# TPA3255.net
KiCad netlist of a schematic drawn in EAGLE
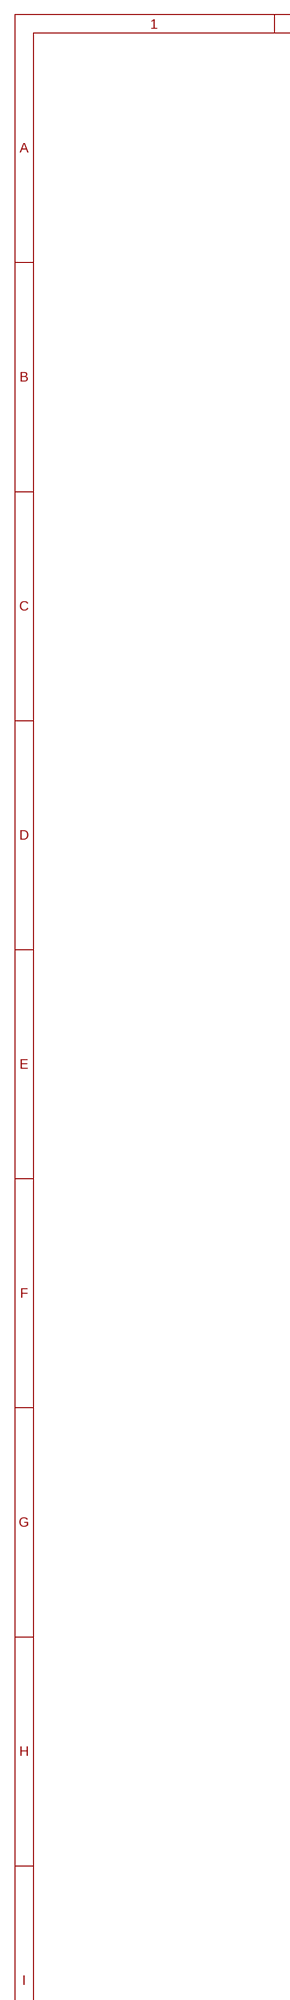
[diagram p0: schematic, sheet 1, part 1 of 2]
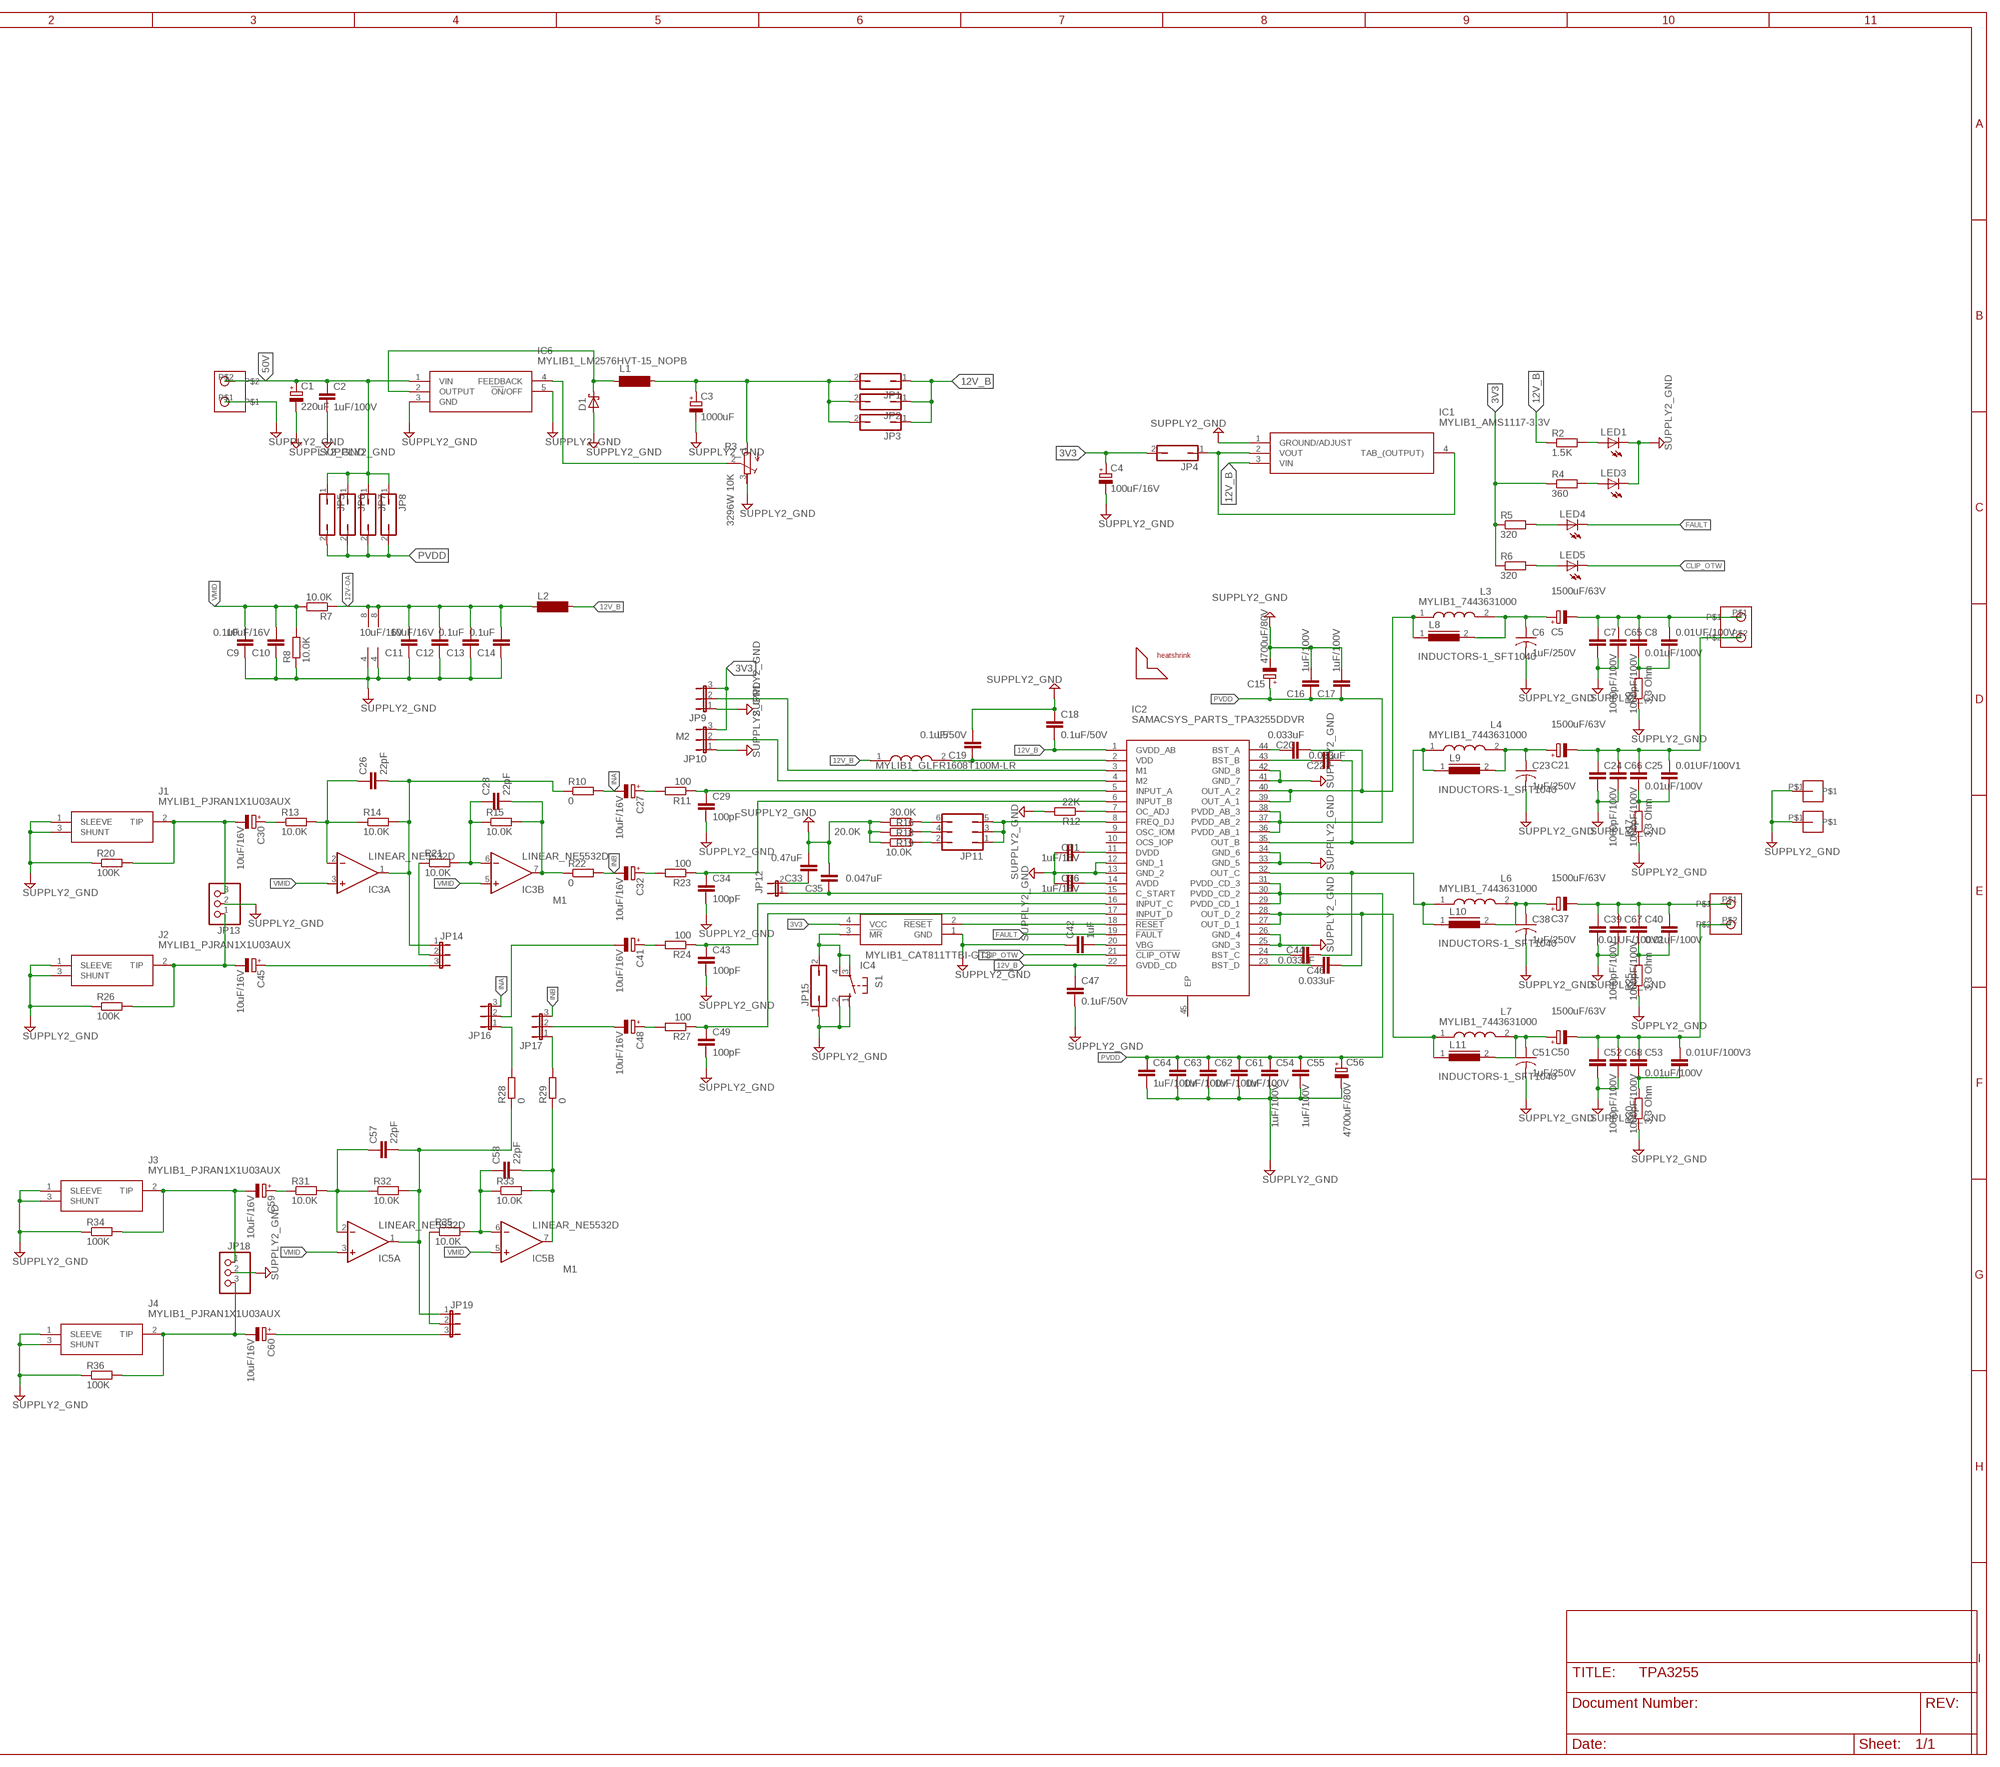
[diagram p1: schematic, sheet 1, part 2 of 2]

(export (version "E")
  (design (tool "Eeschema 10.0.6"))
  (components
    (comp (ref "0.01UF/100V")
      (value "RCL_C-EU102-054X133")
      (footprint "eagle-import:RCL_C102-054X133")
      (libsource (lib "eagle-import") (part "RCL_C-EU102-054X133"))
    )
    (comp (ref "0.01UF/100V1")
      (value "RCL_C-EU102-054X133")
      (footprint "eagle-import:RCL_C102-054X133")
      (libsource (lib "eagle-import") (part "RCL_C-EU102-054X133"))
    )
    (comp (ref "0.01UF/100V2")
      (value "RCL_C-EU102-054X133")
      (footprint "eagle-import:RCL_C102-054X133")
      (libsource (lib "eagle-import") (part "RCL_C-EU102-054X133"))
    )
    (comp (ref "0.01UF/100V3")
      (value "RCL_C-EU102-054X133")
      (footprint "eagle-import:RCL_C102-054X133")
      (libsource (lib "eagle-import") (part "RCL_C-EU102-054X133"))
    )
    (comp (ref "C1")
      (value "220uF")
      (footprint "eagle-import:RCL_E7,5-18")
      (libsource (lib "eagle-import") (part "RCL_CPOL-EUE7.5-18"))
    )
    (comp (ref "C2")
      (value "1uF/100V")
      (footprint "eagle-import:RCL_C150-054X183")
      (libsource (lib "eagle-import") (part "RCL_C-EU150-054X183"))
    )
    (comp (ref "C3")
      (value "1000uF")
      (footprint "eagle-import:RCL_E5-10,5")
      (libsource (lib "eagle-import") (part "RCL_CPOL-EUE5-10.5"))
    )
    (comp (ref "C4")
      (value "100uF/16V")
      (footprint "eagle-import:RESISTOR_PANASONIC_B_1")
      (libsource (lib "eagle-import") (part "RESISTOR_CPOL-EU?{colon}1B"))
    )
    (comp (ref "C5")
      (value "1500uF/63V")
      (footprint "eagle-import:RCL_EB22,5D")
      (libsource (lib "eagle-import") (part "RCL_CPOL-EUE10-22.5"))
    )
    (comp (ref "C6")
      (value "1uF/250V")
      (footprint "eagle-import:RCL_C225-108X268")
      (libsource (lib "eagle-import") (part "RCL_C-US225-108X268"))
    )
    (comp (ref "C7")
      (value "1000pF/100V")
      (footprint "eagle-import:RCL_C1206")
      (libsource (lib "eagle-import") (part "RCL_C-EUC1206"))
    )
    (comp (ref "C8")
      (value "0.01uF/100V")
      (footprint "eagle-import:RCL_C0603")
      (libsource (lib "eagle-import") (part "RCL_C-EUC0603"))
    )
    (comp (ref "C9")
      (value "0.1uF")
      (footprint "eagle-import:RCL_C0805")
      (libsource (lib "eagle-import") (part "RCL_C-EUC0805"))
    )
    (comp (ref "C10")
      (value "10uF/16V")
      (footprint "eagle-import:RCL_C0805")
      (libsource (lib "eagle-import") (part "RCL_C-EUC0805"))
    )
    (comp (ref "C11")
      (value "10uF/16V")
      (footprint "eagle-import:RCL_C0805")
      (libsource (lib "eagle-import") (part "RCL_C-EUC0805"))
    )
    (comp (ref "C12")
      (value "10uF/16V")
      (footprint "eagle-import:RCL_C0805")
      (libsource (lib "eagle-import") (part "RCL_C-EUC0805"))
    )
    (comp (ref "C13")
      (value "0.1uF")
      (footprint "eagle-import:RCL_C0805")
      (libsource (lib "eagle-import") (part "RCL_C-EUC0805"))
    )
    (comp (ref "C14")
      (value "0.1uF")
      (footprint "eagle-import:RCL_C0805")
      (libsource (lib "eagle-import") (part "RCL_C-EUC0805"))
    )
    (comp (ref "C15")
      (value "4700uF/80V")
      (footprint "eagle-import:RCL_EB35D")
      (libsource (lib "eagle-import") (part "RCL_CPOL-EUE10-35"))
    )
    (comp (ref "C16")
      (value "1uF/100V")
      (footprint "eagle-import:RCL_C150-054X183")
      (libsource (lib "eagle-import") (part "RCL_C-EU150-054X183"))
    )
    (comp (ref "C17")
      (value "1uF/100V")
      (footprint "eagle-import:RCL_C150-054X183")
      (libsource (lib "eagle-import") (part "RCL_C-EU150-054X183"))
    )
    (comp (ref "C18")
      (value "0.1uF/50V")
      (footprint "eagle-import:RCL_C0603")
      (libsource (lib "eagle-import") (part "RCL_C-EUC0603"))
    )
    (comp (ref "C19")
      (value "0.1uF/50V")
      (footprint "eagle-import:RCL_C0603")
      (libsource (lib "eagle-import") (part "RCL_C-EUC0603"))
    )
    (comp (ref "C20")
      (value "0.033uF")
      (footprint "eagle-import:RCL_C0603K")
      (libsource (lib "eagle-import") (part "RCL_C-EUC0603K"))
    )
    (comp (ref "C21")
      (value "1500uF/63V")
      (footprint "eagle-import:RCL_EB22,5D")
      (libsource (lib "eagle-import") (part "RCL_CPOL-EUE10-22.5"))
    )
    (comp (ref "C22")
      (value "0.033uF")
      (footprint "eagle-import:RCL_C0603K")
      (libsource (lib "eagle-import") (part "RCL_C-EUC0603K"))
    )
    (comp (ref "C23")
      (value "1uF/250V")
      (footprint "eagle-import:RCL_C225-108X268")
      (libsource (lib "eagle-import") (part "RCL_C-US225-108X268"))
    )
    (comp (ref "C24")
      (value "1000pF/100V")
      (footprint "eagle-import:RCL_C1206")
      (libsource (lib "eagle-import") (part "RCL_C-EUC1206"))
    )
    (comp (ref "C25")
      (value "0.01uF/100V")
      (footprint "eagle-import:RCL_C0603")
      (libsource (lib "eagle-import") (part "RCL_C-EUC0603"))
    )
    (comp (ref "C26")
      (value "22pF")
      (footprint "eagle-import:RCL_C0805")
      (libsource (lib "eagle-import") (part "RCL_C-EUC0805"))
    )
    (comp (ref "C27")
      (value "10uF/16V")
      (footprint "eagle-import:RCL_PANASONIC_B")
      (libsource (lib "eagle-import") (part "RCL_CPOL-EUB"))
    )
    (comp (ref "C28")
      (value "22pF")
      (footprint "eagle-import:RCL_C0805")
      (libsource (lib "eagle-import") (part "RCL_C-EUC0805"))
    )
    (comp (ref "C29")
      (value "100pF")
      (footprint "eagle-import:RCL_C0805")
      (libsource (lib "eagle-import") (part "RCL_C-EUC0805"))
    )
    (comp (ref "C30")
      (value "10uF/16V")
      (footprint "eagle-import:RCL_PANASONIC_B")
      (libsource (lib "eagle-import") (part "RCL_CPOL-EUB"))
    )
    (comp (ref "C31")
      (value "1uF/16V")
      (footprint "eagle-import:RCL_C0603")
      (libsource (lib "eagle-import") (part "RCL_C-EUC0603"))
    )
    (comp (ref "C32")
      (value "10uF/16V")
      (footprint "eagle-import:RCL_PANASONIC_B")
      (libsource (lib "eagle-import") (part "RCL_CPOL-EUB"))
    )
    (comp (ref "C33")
      (value "0.47uF")
      (footprint "eagle-import:RCL_C0603")
      (libsource (lib "eagle-import") (part "RCL_C-EUC0603"))
    )
    (comp (ref "C34")
      (value "100pF")
      (footprint "eagle-import:RCL_C0805")
      (libsource (lib "eagle-import") (part "RCL_C-EUC0805"))
    )
    (comp (ref "C35")
      (value "0.047uF")
      (footprint "eagle-import:RCL_C0805")
      (libsource (lib "eagle-import") (part "RCL_C-EUC0805"))
    )
    (comp (ref "C36")
      (value "1uF/16V")
      (footprint "eagle-import:RCL_C0603")
      (libsource (lib "eagle-import") (part "RCL_C-EUC0603"))
    )
    (comp (ref "C37")
      (value "1500uF/63V")
      (footprint "eagle-import:RCL_EB22,5D")
      (libsource (lib "eagle-import") (part "RCL_CPOL-EUE10-22.5"))
    )
    (comp (ref "C38")
      (value "1uF/250V")
      (footprint "eagle-import:RCL_C225-108X268")
      (libsource (lib "eagle-import") (part "RCL_C-US225-108X268"))
    )
    (comp (ref "C39")
      (value "1000pF/100V")
      (footprint "eagle-import:RCL_C1206")
      (libsource (lib "eagle-import") (part "RCL_C-EUC1206"))
    )
    (comp (ref "C40")
      (value "0.01uF/100V")
      (footprint "eagle-import:RCL_C0603")
      (libsource (lib "eagle-import") (part "RCL_C-EUC0603"))
    )
    (comp (ref "C41")
      (value "10uF/16V")
      (footprint "eagle-import:RCL_PANASONIC_B")
      (libsource (lib "eagle-import") (part "RCL_CPOL-EUB"))
    )
    (comp (ref "C42")
      (value "1uF")
      (footprint "eagle-import:RESISTOR_C0603_1")
      (libsource (lib "eagle-import") (part "RESISTOR_C-EU?{colon}1C0603"))
    )
    (comp (ref "C43")
      (value "100pF")
      (footprint "eagle-import:RCL_C0805")
      (libsource (lib "eagle-import") (part "RCL_C-EUC0805"))
    )
    (comp (ref "C44")
      (value "0.033uF")
      (footprint "eagle-import:RCL_C0603K")
      (libsource (lib "eagle-import") (part "RCL_C-EUC0603K"))
    )
    (comp (ref "C45")
      (value "10uF/16V")
      (footprint "eagle-import:RCL_PANASONIC_B")
      (libsource (lib "eagle-import") (part "RCL_CPOL-EUB"))
    )
    (comp (ref "C46")
      (value "0.033uF")
      (footprint "eagle-import:RCL_C0603K")
      (libsource (lib "eagle-import") (part "RCL_C-EUC0603K"))
    )
    (comp (ref "C47")
      (value "0.1uF/50V")
      (footprint "eagle-import:RCL_C0603")
      (libsource (lib "eagle-import") (part "RCL_C-EUC0603"))
    )
    (comp (ref "C48")
      (value "10uF/16V")
      (footprint "eagle-import:RCL_PANASONIC_B")
      (libsource (lib "eagle-import") (part "RCL_CPOL-EUB"))
    )
    (comp (ref "C49")
      (value "100pF")
      (footprint "eagle-import:RCL_C0805")
      (libsource (lib "eagle-import") (part "RCL_C-EUC0805"))
    )
    (comp (ref "C50")
      (value "1500uF/63V")
      (footprint "eagle-import:RCL_EB22,5D")
      (libsource (lib "eagle-import") (part "RCL_CPOL-EUE10-22.5"))
    )
    (comp (ref "C51")
      (value "1uF/250V")
      (footprint "eagle-import:RCL_C225-108X268")
      (libsource (lib "eagle-import") (part "RCL_C-US225-108X268"))
    )
    (comp (ref "C52")
      (value "1000pF/100V")
      (footprint "eagle-import:RCL_C1206")
      (libsource (lib "eagle-import") (part "RCL_C-EUC1206"))
    )
    (comp (ref "C53")
      (value "0.01uF/100V")
      (footprint "eagle-import:RCL_C0603")
      (libsource (lib "eagle-import") (part "RCL_C-EUC0603"))
    )
    (comp (ref "C54")
      (value "1uF/100V")
      (footprint "eagle-import:RCL_C150-054X183")
      (libsource (lib "eagle-import") (part "RCL_C-EU150-054X183"))
    )
    (comp (ref "C55")
      (value "1uF/100V")
      (footprint "eagle-import:RCL_C150-054X183")
      (libsource (lib "eagle-import") (part "RCL_C-EU150-054X183"))
    )
    (comp (ref "C56")
      (value "4700uF/80V")
      (footprint "eagle-import:RCL_EB35D")
      (libsource (lib "eagle-import") (part "RCL_CPOL-EUE10-35"))
    )
    (comp (ref "C57")
      (value "22pF")
      (footprint "eagle-import:RCL_C0805")
      (libsource (lib "eagle-import") (part "RCL_C-EUC0805"))
    )
    (comp (ref "C58")
      (value "22pF")
      (footprint "eagle-import:RCL_C0805")
      (libsource (lib "eagle-import") (part "RCL_C-EUC0805"))
    )
    (comp (ref "C59")
      (value "10uF/16V")
      (footprint "eagle-import:RCL_PANASONIC_B")
      (libsource (lib "eagle-import") (part "RCL_CPOL-EUB"))
    )
    (comp (ref "C60")
      (value "10uF/16V")
      (footprint "eagle-import:RCL_PANASONIC_B")
      (libsource (lib "eagle-import") (part "RCL_CPOL-EUB"))
    )
    (comp (ref "C61")
      (value "1uF/100V")
      (footprint "eagle-import:RCL_C1206")
      (libsource (lib "eagle-import") (part "RCL_C-EUC1206"))
    )
    (comp (ref "C62")
      (value "1uF/100V")
      (footprint "eagle-import:RCL_C1206")
      (libsource (lib "eagle-import") (part "RCL_C-EUC1206"))
    )
    (comp (ref "C63")
      (value "1uF/100V")
      (footprint "eagle-import:RCL_C1206")
      (libsource (lib "eagle-import") (part "RCL_C-EUC1206"))
    )
    (comp (ref "C64")
      (value "1uF/100V")
      (footprint "eagle-import:RCL_C1206")
      (libsource (lib "eagle-import") (part "RCL_C-EUC1206"))
    )
    (comp (ref "C65")
      (value "1000pF/100V")
      (footprint "eagle-import:RCL_C050-025X075")
      (libsource (lib "eagle-import") (part "RCL_C-EU050-025X075"))
    )
    (comp (ref "C66")
      (value "1000pF/100V")
      (footprint "eagle-import:RCL_C050-025X075")
      (libsource (lib "eagle-import") (part "RCL_C-EU050-025X075"))
    )
    (comp (ref "C67")
      (value "1000pF/100V")
      (footprint "eagle-import:RCL_C050-025X075")
      (libsource (lib "eagle-import") (part "RCL_C-EU050-025X075"))
    )
    (comp (ref "C68")
      (value "1000pF/100V")
      (footprint "eagle-import:RCL_C050-025X075")
      (libsource (lib "eagle-import") (part "RCL_C-EU050-025X075"))
    )
    (comp (ref "D1")
      (value "DIODE_SCHOTTKY-DIODESMD")
      (footprint "eagle-import:DIODE_SMB")
      (libsource (lib "eagle-import") (part "DIODE_SCHOTTKY-DIODESMD"))
    )
    (comp (ref "H1")
      (value "28x28mm")
      (footprint "eagle-import:MYLIB1_HEATSHRINK-28X28MM")
      (libsource (lib "eagle-import") (part "MYLIB1_HEATSHRINK-28X28MM"))
    )
    (comp (ref "IC1")
      (value "MYLIB1_AMS1117-3.3V")
      (footprint "eagle-import:MYLIB1_SOT229P700X180-4N")
      (fields (field (name "MANUFACTURER_PART_NUMBER") "ams1117-3.3v"))
      (libsource (lib "eagle-import") (part "MYLIB1_AMS1117-3.3V"))
    )
    (comp (ref "IC2")
      (value "SAMACSYS_PARTS_TPA3255DDVR")
      (footprint "eagle-import:SAMACSYS_PARTS_SOP64P810X120-45N")
      (fields (field (name "ARROW_PART_NUMBER") "TPA3255DDVR"))
      (libsource (lib "eagle-import") (part "SAMACSYS_PARTS_TPA3255DDVR"))
    )
    (comp (ref "IC3")
      (value "LINEAR_NE5532D")
      (footprint "eagle-import:LINEAR_SO08")
      (libsource (lib "eagle-import") (part "LINEAR_NE5532D"))
    )
    (comp (ref "IC4")
      (value "MYLIB1_CAT811TTBI-GT3")
      (footprint "eagle-import:MYLIB1_4-PIN-SOT-143(BI-SUFFIX-CASE-5")
      (fields
        (field (name "MANUFACTURER_PART_NUMBER") "CAT811TTBI-GT3")
        (field (name "MOUSER_PART_NUMBER") "698-CAT811TTBI-GT3")
        (field (name "RS_PART_NUMBER") "7893929P")
      )
      (libsource (lib "eagle-import") (part "MYLIB1_CAT811TTBI-GT3"))
    )
    (comp (ref "IC5")
      (value "LINEAR_NE5532D")
      (footprint "eagle-import:LINEAR_SO08")
      (libsource (lib "eagle-import") (part "LINEAR_NE5532D"))
    )
    (comp (ref "IC6")
      (value "MYLIB1_LM2576HVT-15_NOPB")
      (footprint "eagle-import:MYLIB1_LM2576HVT15NOPB")
      (fields
        (field (name "MANUFACTURER_PART_NUMBER") "LM2576HVT-15/NOPB")
        (field (name "MOUSER_PART_NUMBER") "926-LM2576HVT-15NOPB")
        (field (name "RS_PART_NUMBER") "1628191")
      )
      (libsource (lib "eagle-import") (part "MYLIB1_LM2576HVT-15_NOPB"))
    )
    (comp (ref "J1")
      (value "MYLIB1_PJRAN1X1U03AUX")
      (footprint "eagle-import:MYLIB1_PJRAN1X1U03AUX")
      (fields
        (field (name "MANUFACTURER_PART_NUMBER") "PJRAN1X1U03AUX")
        (field (name "MOUSER_PART_NUMBER") "502-PJRAN1X1U03AUX")
      )
      (libsource (lib "eagle-import") (part "MYLIB1_PJRAN1X1U03AUX"))
    )
    (comp (ref "J2")
      (value "MYLIB1_PJRAN1X1U03AUX")
      (footprint "eagle-import:MYLIB1_PJRAN1X1U03AUX")
      (fields
        (field (name "MANUFACTURER_PART_NUMBER") "PJRAN1X1U03AUX")
        (field (name "MOUSER_PART_NUMBER") "502-PJRAN1X1U03AUX")
      )
      (libsource (lib "eagle-import") (part "MYLIB1_PJRAN1X1U03AUX"))
    )
    (comp (ref "J3")
      (value "MYLIB1_PJRAN1X1U03AUX")
      (footprint "eagle-import:MYLIB1_PJRAN1X1U03AUX")
      (fields
        (field (name "MANUFACTURER_PART_NUMBER") "PJRAN1X1U03AUX")
        (field (name "MOUSER_PART_NUMBER") "502-PJRAN1X1U03AUX")
      )
      (libsource (lib "eagle-import") (part "MYLIB1_PJRAN1X1U03AUX"))
    )
    (comp (ref "J4")
      (value "MYLIB1_PJRAN1X1U03AUX")
      (footprint "eagle-import:MYLIB1_PJRAN1X1U03AUX")
      (fields
        (field (name "MANUFACTURER_PART_NUMBER") "PJRAN1X1U03AUX")
        (field (name "MOUSER_PART_NUMBER") "502-PJRAN1X1U03AUX")
      )
      (libsource (lib "eagle-import") (part "MYLIB1_PJRAN1X1U03AUX"))
    )
    (comp (ref "JP1")
      (value "JUMPER_JP1Q")
      (footprint "eagle-import:JUMPER_JP1")
      (libsource (lib "eagle-import") (part "JUMPER_JP1Q"))
    )
    (comp (ref "JP2")
      (value "JUMPER_JP1Q")
      (footprint "eagle-import:JUMPER_JP1")
      (libsource (lib "eagle-import") (part "JUMPER_JP1Q"))
    )
    (comp (ref "JP3")
      (value "JUMPER_JP1Q")
      (footprint "eagle-import:JUMPER_JP1")
      (libsource (lib "eagle-import") (part "JUMPER_JP1Q"))
    )
    (comp (ref "JP4")
      (value "JUMPER_JP1Q")
      (footprint "eagle-import:JUMPER_JP1")
      (libsource (lib "eagle-import") (part "JUMPER_JP1Q"))
    )
    (comp (ref "JP5")
      (value "JUMPER_JP1Q")
      (footprint "eagle-import:JUMPER_JP1")
      (libsource (lib "eagle-import") (part "JUMPER_JP1Q"))
    )
    (comp (ref "JP6")
      (value "JUMPER_JP1Q")
      (footprint "eagle-import:JUMPER_JP1")
      (libsource (lib "eagle-import") (part "JUMPER_JP1Q"))
    )
    (comp (ref "JP7")
      (value "JUMPER_JP1Q")
      (footprint "eagle-import:JUMPER_JP1")
      (libsource (lib "eagle-import") (part "JUMPER_JP1Q"))
    )
    (comp (ref "JP8")
      (value "JUMPER_JP1Q")
      (footprint "eagle-import:JUMPER_JP1")
      (libsource (lib "eagle-import") (part "JUMPER_JP1Q"))
    )
    (comp (ref "JP9")
      (value "JUMPER_JP2E")
      (footprint "eagle-import:JUMPER_JP2")
      (libsource (lib "eagle-import") (part "JUMPER_JP2E"))
    )
    (comp (ref "JP10")
      (value "JUMPER_JP2E")
      (footprint "eagle-import:JUMPER_JP2")
      (libsource (lib "eagle-import") (part "JUMPER_JP2E"))
    )
    (comp (ref "JP11")
      (value "JUMPER_JP3Q")
      (footprint "eagle-import:JUMPER_JP3Q")
      (libsource (lib "eagle-import") (part "JUMPER_JP3Q"))
    )
    (comp (ref "JP12")
      (value "JUMPER_JP1E")
      (footprint "eagle-import:JUMPER_JP1")
      (libsource (lib "eagle-import") (part "JUMPER_JP1E"))
    )
    (comp (ref "JP13")
      (value "PINHEAD_PINHD-1X3")
      (footprint "eagle-import:PINHEAD_1X03")
      (libsource (lib "eagle-import") (part "PINHEAD_PINHD-1X3"))
    )
    (comp (ref "JP14")
      (value "JUMPER_JP2E")
      (footprint "eagle-import:JUMPER_JP2")
      (libsource (lib "eagle-import") (part "JUMPER_JP2E"))
    )
    (comp (ref "JP15")
      (value "JUMPER_JP1Q")
      (footprint "eagle-import:JUMPER_JP1")
      (libsource (lib "eagle-import") (part "JUMPER_JP1Q"))
    )
    (comp (ref "JP16")
      (value "JUMPER_JP2E")
      (footprint "eagle-import:JUMPER_JP2")
      (libsource (lib "eagle-import") (part "JUMPER_JP2E"))
    )
    (comp (ref "JP17")
      (value "JUMPER_JP2E")
      (footprint "eagle-import:JUMPER_JP2")
      (libsource (lib "eagle-import") (part "JUMPER_JP2E"))
    )
    (comp (ref "JP18")
      (value "PINHEAD_PINHD-1X3")
      (footprint "eagle-import:PINHEAD_1X03")
      (libsource (lib "eagle-import") (part "PINHEAD_PINHD-1X3"))
    )
    (comp (ref "JP19")
      (value "JUMPER_JP2E")
      (footprint "eagle-import:JUMPER_JP2")
      (libsource (lib "eagle-import") (part "JUMPER_JP2E"))
    )
    (comp (ref "L1")
      (value "INDUCTOR-NEOSID_BS11")
      (footprint "eagle-import:INDUCTOR-NEOSID_BS11")
      (libsource (lib "eagle-import") (part "INDUCTOR-NEOSID_BS11"))
    )
    (comp (ref "L2")
      (value "INDUCTOR-NEOSID_BS11")
      (footprint "eagle-import:INDUCTOR-NEOSID_BS11")
      (libsource (lib "eagle-import") (part "INDUCTOR-NEOSID_BS11"))
    )
    (comp (ref "L3")
      (value "MYLIB1_7443631000")
      (footprint "eagle-import:MYLIB1_WE-HCF_201322")
      (fields
        (field (name "MANUFACTURER_PART_NUMBER") "7443631000")
        (field (name "MOUSER_PART_NUMBER") "710-7443631000")
        (field (name "RS_PART_NUMBER") "7445047P")
      )
      (libsource (lib "eagle-import") (part "MYLIB1_7443631000"))
    )
    (comp (ref "L4")
      (value "MYLIB1_7443631000")
      (footprint "eagle-import:MYLIB1_WE-HCF_201322")
      (fields
        (field (name "MANUFACTURER_PART_NUMBER") "7443631000")
        (field (name "MOUSER_PART_NUMBER") "710-7443631000")
        (field (name "RS_PART_NUMBER") "7445047P")
      )
      (libsource (lib "eagle-import") (part "MYLIB1_7443631000"))
    )
    (comp (ref "L5")
      (value "MYLIB1_GLFR1608T100M-LR")
      (footprint "eagle-import:MYLIB1_INDC1608X100N")
      (fields
        (field (name "MANUFACTURER_PART_NUMBER") "GLFR1608T100M-LR")
        (field (name "MOUSER_PART_NUMBER") "810-GLFR1608T100M-LR")
        (field (name "RS_PART_NUMBER") "6446626")
      )
      (libsource (lib "eagle-import") (part "MYLIB1_GLFR1608T100M-LR"))
    )
    (comp (ref "L6")
      (value "MYLIB1_7443631000")
      (footprint "eagle-import:MYLIB1_WE-HCF_201322")
      (fields
        (field (name "MANUFACTURER_PART_NUMBER") "7443631000")
        (field (name "MOUSER_PART_NUMBER") "710-7443631000")
        (field (name "RS_PART_NUMBER") "7445047P")
      )
      (libsource (lib "eagle-import") (part "MYLIB1_7443631000"))
    )
    (comp (ref "L7")
      (value "MYLIB1_7443631000")
      (footprint "eagle-import:MYLIB1_WE-HCF_201322")
      (fields
        (field (name "MANUFACTURER_PART_NUMBER") "7443631000")
        (field (name "MOUSER_PART_NUMBER") "710-7443631000")
        (field (name "RS_PART_NUMBER") "7445047P")
      )
      (libsource (lib "eagle-import") (part "MYLIB1_7443631000"))
    )
    (comp (ref "L8")
      (value "INDUCTORS-1_SFT1040")
      (footprint "eagle-import:INDUCTORS-1_SFT1040")
      (libsource (lib "eagle-import") (part "INDUCTORS-1_SFT1040"))
    )
    (comp (ref "L9")
      (value "INDUCTORS-1_SFT1040")
      (footprint "eagle-import:INDUCTORS-1_SFT1040")
      (libsource (lib "eagle-import") (part "INDUCTORS-1_SFT1040"))
    )
    (comp (ref "L10")
      (value "INDUCTORS-1_SFT1040")
      (footprint "eagle-import:INDUCTORS-1_SFT1040")
      (libsource (lib "eagle-import") (part "INDUCTORS-1_SFT1040"))
    )
    (comp (ref "L11")
      (value "INDUCTORS-1_SFT1040")
      (footprint "eagle-import:INDUCTORS-1_SFT1040")
      (libsource (lib "eagle-import") (part "INDUCTORS-1_SFT1040"))
    )
    (comp (ref "LED1")
      (value "LED_LEDCHIP-LED0805")
      (footprint "eagle-import:LED_CHIP-LED0805")
      (libsource (lib "eagle-import") (part "LED_LEDCHIP-LED0805"))
    )
    (comp (ref "LED3")
      (value "LED_LEDCHIP-LED0805")
      (footprint "eagle-import:LED_CHIP-LED0805")
      (libsource (lib "eagle-import") (part "LED_LEDCHIP-LED0805"))
    )
    (comp (ref "LED4")
      (value "LED_LEDCHIP-LED0805")
      (footprint "eagle-import:LED_CHIP-LED0805")
      (libsource (lib "eagle-import") (part "LED_LEDCHIP-LED0805"))
    )
    (comp (ref "LED5")
      (value "LED_LEDCHIP-LED0805")
      (footprint "eagle-import:LED_CHIP-LED0805")
      (libsource (lib "eagle-import") (part "LED_LEDCHIP-LED0805"))
    )
    (comp (ref "R2")
      (value "1.5K")
      (footprint "eagle-import:RCL_M0805")
      (libsource (lib "eagle-import") (part "RCL_R-EU_M0805"))
    )
    (comp (ref "R3")
      (value "3296W 10K")
      (footprint "eagle-import:RCL_RTRIM3296W")
      (libsource (lib "eagle-import") (part "RCL_R-TRIMM3296W"))
    )
    (comp (ref "R4")
      (value "360")
      (footprint "eagle-import:RCL_M0805")
      (libsource (lib "eagle-import") (part "RCL_R-EU_M0805"))
    )
    (comp (ref "R5")
      (value "320")
      (footprint "eagle-import:RCL_M0805")
      (libsource (lib "eagle-import") (part "RCL_R-EU_M0805"))
    )
    (comp (ref "R6")
      (value "320")
      (footprint "eagle-import:RCL_M0805")
      (libsource (lib "eagle-import") (part "RCL_R-EU_M0805"))
    )
    (comp (ref "R7")
      (value "10.0K")
      (footprint "eagle-import:RESISTOR_M0805_1")
      (libsource (lib "eagle-import") (part "RESISTOR_R-EU_?{colon}1M0805"))
    )
    (comp (ref "R8")
      (value "10.0K")
      (footprint "eagle-import:RESISTOR_M0805_1")
      (libsource (lib "eagle-import") (part "RESISTOR_R-EU_?{colon}1M0805"))
    )
    (comp (ref "R9")
      (value "3.3 Ohm")
      (footprint "eagle-import:RESISTOR_R0805_1")
      (libsource (lib "eagle-import") (part "RESISTOR_R-EU_?{colon}1R0805"))
    )
    (comp (ref "R10")
      (value "0")
      (footprint "eagle-import:RESISTOR_M0805_1")
      (libsource (lib "eagle-import") (part "RESISTOR_R-EU_?{colon}1M0805"))
    )
    (comp (ref "R11")
      (value "100")
      (footprint "eagle-import:RCL_M0805")
      (libsource (lib "eagle-import") (part "RCL_R-EU_M0805"))
    )
    (comp (ref "R12")
      (value "22K")
      (footprint "eagle-import:RCL_M0805")
      (libsource (lib "eagle-import") (part "RCL_R-EU_M0805"))
    )
    (comp (ref "R13")
      (value "10.0K")
      (footprint "eagle-import:RESISTOR_M0805_1")
      (libsource (lib "eagle-import") (part "RESISTOR_R-EU_?{colon}1M0805"))
    )
    (comp (ref "R14")
      (value "10.0K")
      (footprint "eagle-import:RESISTOR_M0805_1")
      (libsource (lib "eagle-import") (part "RESISTOR_R-EU_?{colon}1M0805"))
    )
    (comp (ref "R15")
      (value "10.0K")
      (footprint "eagle-import:RESISTOR_M0805_1")
      (libsource (lib "eagle-import") (part "RESISTOR_R-EU_?{colon}1M0805"))
    )
    (comp (ref "R16")
      (value "30.0K")
      (footprint "eagle-import:RCL_R0805")
      (libsource (lib "eagle-import") (part "RCL_R-EU_R0805"))
    )
    (comp (ref "R17")
      (value "3.3 Ohm")
      (footprint "eagle-import:RESISTOR_R0805_1")
      (libsource (lib "eagle-import") (part "RESISTOR_R-EU_?{colon}1R0805"))
    )
    (comp (ref "R18")
      (value "20.0K")
      (footprint "eagle-import:RESISTOR_R0603_1")
      (libsource (lib "eagle-import") (part "RESISTOR_R-EU_?{colon}1R0603"))
    )
    (comp (ref "R19")
      (value "10.0K")
      (footprint "eagle-import:RCL_R0805")
      (libsource (lib "eagle-import") (part "RCL_R-EU_R0805"))
    )
    (comp (ref "R20")
      (value "100K")
      (footprint "eagle-import:RESISTOR_M0805_1")
      (libsource (lib "eagle-import") (part "RESISTOR_R-EU_?{colon}1M0805"))
    )
    (comp (ref "R21")
      (value "10.0K")
      (footprint "eagle-import:RESISTOR_M0805_1")
      (libsource (lib "eagle-import") (part "RESISTOR_R-EU_?{colon}1M0805"))
    )
    (comp (ref "R22")
      (value "0")
      (footprint "eagle-import:RESISTOR_M0805_1")
      (libsource (lib "eagle-import") (part "RESISTOR_R-EU_?{colon}1M0805"))
    )
    (comp (ref "R23")
      (value "100")
      (footprint "eagle-import:RCL_M0805")
      (libsource (lib "eagle-import") (part "RCL_R-EU_M0805"))
    )
    (comp (ref "R24")
      (value "100")
      (footprint "eagle-import:RCL_M0805")
      (libsource (lib "eagle-import") (part "RCL_R-EU_M0805"))
    )
    (comp (ref "R25")
      (value "3.3 Ohm")
      (footprint "eagle-import:RESISTOR_R0805_1")
      (libsource (lib "eagle-import") (part "RESISTOR_R-EU_?{colon}1R0805"))
    )
    (comp (ref "R26")
      (value "100K")
      (footprint "eagle-import:RESISTOR_M0805_1")
      (libsource (lib "eagle-import") (part "RESISTOR_R-EU_?{colon}1M0805"))
    )
    (comp (ref "R27")
      (value "100")
      (footprint "eagle-import:RCL_M0805")
      (libsource (lib "eagle-import") (part "RCL_R-EU_M0805"))
    )
    (comp (ref "R28")
      (value "0")
      (footprint "eagle-import:RESISTOR_M0805_1")
      (libsource (lib "eagle-import") (part "RESISTOR_R-EU_?{colon}1M0805"))
    )
    (comp (ref "R29")
      (value "0")
      (footprint "eagle-import:RESISTOR_M0805_1")
      (libsource (lib "eagle-import") (part "RESISTOR_R-EU_?{colon}1M0805"))
    )
    (comp (ref "R30")
      (value "3.3 Ohm")
      (footprint "eagle-import:RESISTOR_R0805_1")
      (libsource (lib "eagle-import") (part "RESISTOR_R-EU_?{colon}1R0805"))
    )
    (comp (ref "R31")
      (value "10.0K")
      (footprint "eagle-import:RESISTOR_M0805_1")
      (libsource (lib "eagle-import") (part "RESISTOR_R-EU_?{colon}1M0805"))
    )
    (comp (ref "R32")
      (value "10.0K")
      (footprint "eagle-import:RESISTOR_M0805_1")
      (libsource (lib "eagle-import") (part "RESISTOR_R-EU_?{colon}1M0805"))
    )
    (comp (ref "R33")
      (value "10.0K")
      (footprint "eagle-import:RESISTOR_M0805_1")
      (libsource (lib "eagle-import") (part "RESISTOR_R-EU_?{colon}1M0805"))
    )
    (comp (ref "R34")
      (value "100K")
      (footprint "eagle-import:RESISTOR_M0805_1")
      (libsource (lib "eagle-import") (part "RESISTOR_R-EU_?{colon}1M0805"))
    )
    (comp (ref "R35")
      (value "10.0K")
      (footprint "eagle-import:RESISTOR_M0805_1")
      (libsource (lib "eagle-import") (part "RESISTOR_R-EU_?{colon}1M0805"))
    )
    (comp (ref "R36")
      (value "100K")
      (footprint "eagle-import:RESISTOR_M0805_1")
      (libsource (lib "eagle-import") (part "RESISTOR_R-EU_?{colon}1M0805"))
    )
    (comp (ref "S1")
      (value "SWITCH-OMRON_10-XX")
      (footprint "eagle-import:SWITCH-OMRON_B3F-10XX")
      (fields (field (name "MPN") "B3F-1000"))
      (libsource (lib "eagle-import") (part "SWITCH-OMRON_10-XX"))
    )
    (comp (ref "T1")
      (value "MYLIB1_5MM-2PIN-TERMINAL")
      (footprint "eagle-import:MYLIB1_3MM-2PIN-TERMINAL")
      (libsource (lib "eagle-import") (part "MYLIB1_5MM-2PIN-TERMINAL"))
    )
    (comp (ref "T2")
      (value "MYLIB1_5MM-2PIN-TERMINAL")
      (footprint "eagle-import:MYLIB1_3MM-2PIN-TERMINAL")
      (libsource (lib "eagle-import") (part "MYLIB1_5MM-2PIN-TERMINAL"))
    )
    (comp (ref "T4")
      (value "MYLIB1_5MM-2PIN-TERMINAL")
      (footprint "eagle-import:MYLIB1_3MM-2PIN-TERMINAL")
      (libsource (lib "eagle-import") (part "MYLIB1_5MM-2PIN-TERMINAL"))
    )
    (comp (ref "U$1")
      (value "MYLIB1_5MM-1PIN-TERMINAL")
      (footprint "eagle-import:MYLIB1_5MM-1PIN-TERMINAL")
      (libsource (lib "eagle-import") (part "MYLIB1_5MM-1PIN-TERMINAL"))
    )
    (comp (ref "U$2")
      (value "MYLIB1_5MM-1PIN-TERMINAL")
      (footprint "eagle-import:MYLIB1_5MM-1PIN-TERMINAL")
      (libsource (lib "eagle-import") (part "MYLIB1_5MM-1PIN-TERMINAL"))
    )
  )
  (nets
    (net (code "1") (name "3V3") (class "Default")
      (node (ref "C4") (pin "+") (pinfunction "+_+") (pintype "passive"))
      (node (ref "IC4") (pin "4") (pinfunction "VCC_4") (pintype "power_in"))
      (node (ref "JP10") (pin "3") (pinfunction "3_3") (pintype "passive"))
      (node (ref "JP4") (pin "2") (pinfunction "2_2") (pintype "passive"))
      (node (ref "JP9") (pin "3") (pinfunction "3_3") (pintype "passive"))
      (node (ref "R4") (pin "1") (pinfunction "1_1") (pintype "passive"))
      (node (ref "R5") (pin "1") (pinfunction "1_1") (pintype "passive"))
      (node (ref "R6") (pin "1") (pinfunction "1_1") (pintype "passive"))
    )
    (net (code "2") (name "12V-OA") (class "Default")
      (node (ref "C11") (pin "2") (pinfunction "2_2") (pintype "passive"))
      (node (ref "C12") (pin "2") (pinfunction "2_2") (pintype "passive"))
      (node (ref "C13") (pin "2") (pinfunction "2_2") (pintype "passive"))
      (node (ref "C14") (pin "2") (pinfunction "2_2") (pintype "passive"))
      (node (ref "IC3") (pin "8") (pinfunction "V+_8") (pintype "power_in"))
      (node (ref "IC5") (pin "8") (pinfunction "V+_8") (pintype "power_in"))
      (node (ref "L2") (pin "1") (pinfunction "1_1") (pintype "passive"))
      (node (ref "R7") (pin "1") (pinfunction "1_1") (pintype "passive"))
    )
    (net (code "3") (name "12V_B") (class "Default")
      (node (ref "C18") (pin "2") (pinfunction "2_2") (pintype "passive"))
      (node (ref "C47") (pin "1") (pinfunction "1_1") (pintype "passive"))
      (node (ref "IC1") (pin "3") (pinfunction "VIN_3") (pintype "bidirectional"))
      (node (ref "IC2") (pin "1") (pinfunction "GVDD_AB_1") (pintype "power_in"))
      (node (ref "IC2") (pin "22") (pinfunction "GVDD_CD_22") (pintype "power_in"))
      (node (ref "JP1") (pin "1") (pinfunction "1_1") (pintype "passive"))
      (node (ref "JP2") (pin "1") (pinfunction "1_1") (pintype "passive"))
      (node (ref "JP3") (pin "1") (pinfunction "1_1") (pintype "passive"))
      (node (ref "L2") (pin "2") (pinfunction "2_2") (pintype "passive"))
      (node (ref "L5") (pin "1") (pinfunction "1_1") (pintype "bidirectional"))
      (node (ref "R2") (pin "1") (pinfunction "1_1") (pintype "passive"))
    )
    (net (code "4") (name "50V") (class "Default")
      (node (ref "C1") (pin "+") (pinfunction "+_+") (pintype "passive"))
      (node (ref "C2") (pin "1") (pinfunction "1_1") (pintype "passive"))
      (node (ref "IC6") (pin "1") (pinfunction "VIN_1") (pintype "bidirectional"))
      (node (ref "JP5") (pin "1") (pinfunction "1_1") (pintype "passive"))
      (node (ref "JP6") (pin "1") (pinfunction "1_1") (pintype "passive"))
      (node (ref "JP7") (pin "1") (pinfunction "1_1") (pintype "passive"))
      (node (ref "JP8") (pin "1") (pinfunction "1_1") (pintype "passive"))
      (node (ref "T1") (pin "P$2") (pinfunction "P$2_P$2") (pintype "bidirectional"))
    )
    (net (code "5") (name "CLIP_OTW") (class "Default")
      (node (ref "IC2") (pin "21") (pinfunction "~{CLIP_OTW}_21") (pintype "output"))
      (node (ref "LED5") (pin "C") (pinfunction "C_C") (pintype "passive"))
    )
    (net (code "6") (name "FAULT") (class "Default")
      (node (ref "IC2") (pin "19") (pinfunction "~{FAULT}_19") (pintype "output"))
      (node (ref "LED4") (pin "C") (pinfunction "C_C") (pintype "passive"))
    )
    (net (code "7") (name "INA") (class "Default")
      (node (ref "C27") (pin "-") (pinfunction "-_-") (pintype "passive"))
      (node (ref "JP16") (pin "3") (pinfunction "3_3") (pintype "passive"))
      (node (ref "R10") (pin "2") (pinfunction "2_2") (pintype "passive"))
    )
    (net (code "8") (name "INB") (class "Default")
      (node (ref "C32") (pin "-") (pinfunction "-_-") (pintype "passive"))
      (node (ref "JP17") (pin "3") (pinfunction "3_3") (pintype "passive"))
      (node (ref "R22") (pin "2") (pinfunction "2_2") (pintype "passive"))
    )
    (net (code "9") (name "Net-(0.01UF/100V-Pad1)") (class "Default")
      (node (ref "0.01UF/100V") (pin "1") (pinfunction "1_1") (pintype "passive"))
      (node (ref "C5") (pin "-") (pinfunction "-_-") (pintype "passive"))
      (node (ref "C65") (pin "1") (pinfunction "1_1") (pintype "passive"))
      (node (ref "C7") (pin "1") (pinfunction "1_1") (pintype "passive"))
      (node (ref "C8") (pin "1") (pinfunction "1_1") (pintype "passive"))
      (node (ref "T2") (pin "P$1") (pinfunction "P$1_P$1") (pintype "bidirectional"))
    )
    (net (code "10") (name "Net-(0.01UF/100V-Pad2)") (class "Default")
      (node (ref "0.01UF/100V") (pin "2") (pinfunction "2_2") (pintype "passive"))
      (node (ref "C8") (pin "2") (pinfunction "2_2") (pintype "passive"))
      (node (ref "R9") (pin "2") (pinfunction "2_2") (pintype "passive"))
    )
    (net (code "11") (name "Net-(0.01UF/100V1-Pad1)") (class "Default")
      (node (ref "0.01UF/100V1") (pin "1") (pinfunction "1_1") (pintype "passive"))
      (node (ref "C21") (pin "-") (pinfunction "-_-") (pintype "passive"))
      (node (ref "C24") (pin "1") (pinfunction "1_1") (pintype "passive"))
      (node (ref "C25") (pin "1") (pinfunction "1_1") (pintype "passive"))
      (node (ref "C66") (pin "1") (pinfunction "1_1") (pintype "passive"))
      (node (ref "T2") (pin "P$2") (pinfunction "P$2_P$2") (pintype "bidirectional"))
    )
    (net (code "12") (name "Net-(0.01UF/100V1-Pad2)") (class "Default")
      (node (ref "0.01UF/100V1") (pin "2") (pinfunction "2_2") (pintype "passive"))
      (node (ref "C25") (pin "2") (pinfunction "2_2") (pintype "passive"))
      (node (ref "R17") (pin "2") (pinfunction "2_2") (pintype "passive"))
    )
    (net (code "13") (name "Net-(0.01UF/100V2-Pad1)") (class "Default")
      (node (ref "0.01UF/100V2") (pin "1") (pinfunction "1_1") (pintype "passive"))
      (node (ref "C40") (pin "2") (pinfunction "2_2") (pintype "passive"))
      (node (ref "R25") (pin "2") (pinfunction "2_2") (pintype "passive"))
    )
    (net (code "14") (name "Net-(0.01UF/100V2-Pad2)") (class "Default")
      (node (ref "0.01UF/100V2") (pin "2") (pinfunction "2_2") (pintype "passive"))
      (node (ref "C37") (pin "-") (pinfunction "-_-") (pintype "passive"))
      (node (ref "C39") (pin "1") (pinfunction "1_1") (pintype "passive"))
      (node (ref "C40") (pin "1") (pinfunction "1_1") (pintype "passive"))
      (node (ref "C67") (pin "1") (pinfunction "1_1") (pintype "passive"))
      (node (ref "T4") (pin "P$1") (pinfunction "P$1_P$1") (pintype "bidirectional"))
    )
    (net (code "15") (name "Net-(0.01UF/100V3-Pad1)") (class "Default")
      (node (ref "0.01UF/100V3") (pin "1") (pinfunction "1_1") (pintype "passive"))
      (node (ref "C50") (pin "-") (pinfunction "-_-") (pintype "passive"))
      (node (ref "C52") (pin "1") (pinfunction "1_1") (pintype "passive"))
      (node (ref "C53") (pin "1") (pinfunction "1_1") (pintype "passive"))
      (node (ref "C68") (pin "1") (pinfunction "1_1") (pintype "passive"))
      (node (ref "T4") (pin "P$2") (pinfunction "P$2_P$2") (pintype "bidirectional"))
    )
    (net (code "16") (name "Net-(0.01UF/100V3-Pad2)") (class "Default")
      (node (ref "0.01UF/100V3") (pin "2") (pinfunction "2_2") (pintype "passive"))
      (node (ref "C53") (pin "2") (pinfunction "2_2") (pintype "passive"))
      (node (ref "R30") (pin "2") (pinfunction "2_2") (pintype "passive"))
    )
    (net (code "17") (name "Net-(C5-Pad+)") (class "Default")
      (node (ref "C5") (pin "+") (pinfunction "+_+") (pintype "passive"))
      (node (ref "C6") (pin "1") (pinfunction "1_1") (pintype "passive"))
      (node (ref "L3") (pin "2") (pinfunction "2_2") (pintype "bidirectional"))
      (node (ref "L8") (pin "2") (pinfunction "2_2") (pintype "passive"))
    )
    (net (code "18") (name "Net-(C21-Pad+)") (class "Default")
      (node (ref "C21") (pin "+") (pinfunction "+_+") (pintype "passive"))
      (node (ref "C23") (pin "1") (pinfunction "1_1") (pintype "passive"))
      (node (ref "L4") (pin "2") (pinfunction "2_2") (pintype "bidirectional"))
      (node (ref "L9") (pin "2") (pinfunction "2_2") (pintype "passive"))
    )
    (net (code "19") (name "Net-(C27-Pad+)") (class "Default")
      (node (ref "C27") (pin "+") (pinfunction "+_+") (pintype "passive"))
      (node (ref "R11") (pin "2") (pinfunction "2_2") (pintype "passive"))
    )
    (net (code "20") (name "Net-(C30-Pad+)") (class "Default")
      (node (ref "C30") (pin "+") (pinfunction "+_+") (pintype "passive"))
      (node (ref "R13") (pin "1") (pinfunction "1_1") (pintype "passive"))
    )
    (net (code "21") (name "Net-(C32-Pad+)") (class "Default")
      (node (ref "C32") (pin "+") (pinfunction "+_+") (pintype "passive"))
      (node (ref "R23") (pin "2") (pinfunction "2_2") (pintype "passive"))
    )
    (net (code "22") (name "Net-(C33-Pad1)") (class "Default")
      (node (ref "C33") (pin "1") (pinfunction "1_1") (pintype "passive"))
      (node (ref "JP12") (pin "2") (pinfunction "2_2") (pintype "passive"))
    )
    (net (code "23") (name "Net-(C37-Pad+)") (class "Default")
      (node (ref "C37") (pin "+") (pinfunction "+_+") (pintype "passive"))
      (node (ref "C38") (pin "1") (pinfunction "1_1") (pintype "passive"))
      (node (ref "L10") (pin "2") (pinfunction "2_2") (pintype "passive"))
      (node (ref "L6") (pin "2") (pinfunction "2_2") (pintype "bidirectional"))
    )
    (net (code "24") (name "Net-(C41-Pad+)") (class "Default")
      (node (ref "C41") (pin "+") (pinfunction "+_+") (pintype "passive"))
      (node (ref "R24") (pin "2") (pinfunction "2_2") (pintype "passive"))
    )
    (net (code "25") (name "Net-(C41-Pad-)") (class "Default")
      (node (ref "C41") (pin "-") (pinfunction "-_-") (pintype "passive"))
      (node (ref "JP16") (pin "2") (pinfunction "2_2") (pintype "passive"))
    )
    (net (code "26") (name "Net-(C45-Pad+)") (class "Default")
      (node (ref "C45") (pin "+") (pinfunction "+_+") (pintype "passive"))
      (node (ref "JP14") (pin "3") (pinfunction "3_3") (pintype "passive"))
    )
    (net (code "27") (name "Net-(C48-Pad+)") (class "Default")
      (node (ref "C48") (pin "+") (pinfunction "+_+") (pintype "passive"))
      (node (ref "R27") (pin "2") (pinfunction "2_2") (pintype "passive"))
    )
    (net (code "28") (name "Net-(C48-Pad-)") (class "Default")
      (node (ref "C48") (pin "-") (pinfunction "-_-") (pintype "passive"))
      (node (ref "JP17") (pin "2") (pinfunction "2_2") (pintype "passive"))
    )
    (net (code "29") (name "Net-(C50-Pad+)") (class "Default")
      (node (ref "C50") (pin "+") (pinfunction "+_+") (pintype "passive"))
      (node (ref "C51") (pin "1") (pinfunction "1_1") (pintype "passive"))
      (node (ref "L11") (pin "2") (pinfunction "2_2") (pintype "passive"))
      (node (ref "L7") (pin "2") (pinfunction "2_2") (pintype "bidirectional"))
    )
    (net (code "30") (name "Net-(C59-Pad+)") (class "Default")
      (node (ref "C59") (pin "+") (pinfunction "+_+") (pintype "passive"))
      (node (ref "R31") (pin "1") (pinfunction "1_1") (pintype "passive"))
    )
    (net (code "31") (name "Net-(C60-Pad+)") (class "Default")
      (node (ref "C60") (pin "+") (pinfunction "+_+") (pintype "passive"))
      (node (ref "JP19") (pin "3") (pinfunction "3_3") (pintype "passive"))
    )
    (net (code "32") (name "Net-(IC1-TAB_(OUTPUT))") (class "Default")
      (node (ref "IC1") (pin "2") (pinfunction "VOUT_2") (pintype "bidirectional"))
      (node (ref "IC1") (pin "4") (pinfunction "TAB_(OUTPUT)_4") (pintype "bidirectional"))
      (node (ref "JP4") (pin "1") (pinfunction "1_1") (pintype "passive"))
    )
    (net (code "33") (name "Net-(IC2-AVDD)") (class "Default")
      (node (ref "C36") (pin "2") (pinfunction "2_2") (pintype "passive"))
      (node (ref "IC2") (pin "14") (pinfunction "AVDD_14") (pintype "power_in"))
    )
    (net (code "34") (name "Net-(IC2-BST_A)") (class "Default")
      (node (ref "C20") (pin "1") (pinfunction "1_1") (pintype "passive"))
      (node (ref "IC2") (pin "44") (pinfunction "BST_A_44") (pintype "power_in"))
    )
    (net (code "35") (name "Net-(IC2-BST_B)") (class "Default")
      (node (ref "C22") (pin "1") (pinfunction "1_1") (pintype "passive"))
      (node (ref "IC2") (pin "43") (pinfunction "BST_B_43") (pintype "power_in"))
    )
    (net (code "36") (name "Net-(IC2-BST_C)") (class "Default")
      (node (ref "C44") (pin "1") (pinfunction "1_1") (pintype "passive"))
      (node (ref "IC2") (pin "24") (pinfunction "BST_C_24") (pintype "power_in"))
    )
    (net (code "37") (name "Net-(IC2-BST_D)") (class "Default")
      (node (ref "C46") (pin "1") (pinfunction "1_1") (pintype "passive"))
      (node (ref "IC2") (pin "23") (pinfunction "BST_D_23") (pintype "power_in"))
    )
    (net (code "38") (name "Net-(IC2-C_START)") (class "Default")
      (node (ref "C35") (pin "1") (pinfunction "1_1") (pintype "passive"))
      (node (ref "IC2") (pin "15") (pinfunction "C_START_15") (pintype "output"))
      (node (ref "JP12") (pin "1") (pinfunction "1_1") (pintype "passive"))
    )
    (net (code "39") (name "Net-(IC2-DVDD)") (class "Default")
      (node (ref "C31") (pin "2") (pinfunction "2_2") (pintype "passive"))
      (node (ref "IC2") (pin "11") (pinfunction "DVDD_11") (pintype "power_in"))
    )
    (net (code "40") (name "Net-(IC2-FREQ_DJ)") (class "Default")
      (node (ref "IC2") (pin "8") (pinfunction "FREQ_DJ_8") (pintype "output"))
      (node (ref "JP11") (pin "1") (pinfunction "1_1") (pintype "passive"))
      (node (ref "JP11") (pin "3") (pinfunction "3_3") (pintype "passive"))
      (node (ref "JP11") (pin "5") (pinfunction "5_5") (pintype "passive"))
    )
    (net (code "41") (name "Net-(IC2-INPUT_A)") (class "Default")
      (node (ref "C29") (pin "1") (pinfunction "1_1") (pintype "passive"))
      (node (ref "IC2") (pin "5") (pinfunction "INPUT_A_5") (pintype "input"))
      (node (ref "R11") (pin "1") (pinfunction "1_1") (pintype "passive"))
    )
    (net (code "42") (name "Net-(IC2-INPUT_B)") (class "Default")
      (node (ref "C34") (pin "1") (pinfunction "1_1") (pintype "passive"))
      (node (ref "IC2") (pin "6") (pinfunction "INPUT_B_6") (pintype "input"))
      (node (ref "R23") (pin "1") (pinfunction "1_1") (pintype "passive"))
    )
    (net (code "43") (name "Net-(IC2-INPUT_C)") (class "Default")
      (node (ref "C43") (pin "1") (pinfunction "1_1") (pintype "passive"))
      (node (ref "IC2") (pin "16") (pinfunction "INPUT_C_16") (pintype "input"))
      (node (ref "R24") (pin "1") (pinfunction "1_1") (pintype "passive"))
    )
    (net (code "44") (name "Net-(IC2-INPUT_D)") (class "Default")
      (node (ref "C49") (pin "1") (pinfunction "1_1") (pintype "passive"))
      (node (ref "IC2") (pin "17") (pinfunction "INPUT_D_17") (pintype "input"))
      (node (ref "R27") (pin "1") (pinfunction "1_1") (pintype "passive"))
    )
    (net (code "45") (name "Net-(IC2-M1)") (class "Default")
      (node (ref "IC2") (pin "3") (pinfunction "M1_3") (pintype "input"))
      (node (ref "JP9") (pin "2") (pinfunction "2_2") (pintype "passive"))
    )
    (net (code "46") (name "Net-(IC2-M2)") (class "Default")
      (node (ref "IC2") (pin "4") (pinfunction "M2_4") (pintype "input"))
      (node (ref "JP10") (pin "2") (pinfunction "2_2") (pintype "passive"))
    )
    (net (code "47") (name "Net-(IC2-OC_ADJ)") (class "Default")
      (node (ref "IC2") (pin "7") (pinfunction "OC_ADJ_7") (pintype "bidirectional"))
      (node (ref "R12") (pin "1") (pinfunction "1_1") (pintype "passive"))
    )
    (net (code "48") (name "Net-(IC2-OUT_A_1)") (class "Default")
      (node (ref "C20") (pin "2") (pinfunction "2_2") (pintype "passive"))
      (node (ref "IC2") (pin "39") (pinfunction "OUT_A_1_39") (pintype "output"))
      (node (ref "IC2") (pin "40") (pinfunction "OUT_A_2_40") (pintype "output"))
      (node (ref "L3") (pin "1") (pinfunction "1_1") (pintype "bidirectional"))
      (node (ref "L8") (pin "1") (pinfunction "1_1") (pintype "passive"))
    )
    (net (code "49") (name "Net-(IC2-OUT_B)") (class "Default")
      (node (ref "C22") (pin "2") (pinfunction "2_2") (pintype "passive"))
      (node (ref "IC2") (pin "35") (pinfunction "OUT_B_35") (pintype "output"))
      (node (ref "L4") (pin "1") (pinfunction "1_1") (pintype "bidirectional"))
      (node (ref "L9") (pin "1") (pinfunction "1_1") (pintype "passive"))
    )
    (net (code "50") (name "Net-(IC2-OUT_C)") (class "Default")
      (node (ref "C44") (pin "2") (pinfunction "2_2") (pintype "passive"))
      (node (ref "IC2") (pin "32") (pinfunction "OUT_C_32") (pintype "output"))
      (node (ref "L10") (pin "1") (pinfunction "1_1") (pintype "passive"))
      (node (ref "L6") (pin "1") (pinfunction "1_1") (pintype "bidirectional"))
    )
    (net (code "51") (name "Net-(IC2-OUT_D_1)") (class "Default")
      (node (ref "C46") (pin "2") (pinfunction "2_2") (pintype "passive"))
      (node (ref "IC2") (pin "27") (pinfunction "OUT_D_1_27") (pintype "output"))
      (node (ref "IC2") (pin "28") (pinfunction "OUT_D_2_28") (pintype "output"))
      (node (ref "L11") (pin "1") (pinfunction "1_1") (pintype "passive"))
      (node (ref "L7") (pin "1") (pinfunction "1_1") (pintype "bidirectional"))
    )
    (net (code "52") (name "Net-(IC2-VBG)") (class "Default")
      (node (ref "C42") (pin "2") (pinfunction "2_2") (pintype "passive"))
      (node (ref "IC2") (pin "20") (pinfunction "VBG_20") (pintype "power_in"))
    )
    (net (code "53") (name "Net-(IC2-VDD)") (class "Default")
      (node (ref "C19") (pin "1") (pinfunction "1_1") (pintype "passive"))
      (node (ref "IC2") (pin "2") (pinfunction "VDD_2") (pintype "power_in"))
      (node (ref "L5") (pin "2") (pinfunction "2_2") (pintype "bidirectional"))
    )
    (net (code "54") (name "Net-(IC2-~{RESET})") (class "Default")
      (node (ref "IC2") (pin "18") (pinfunction "~{RESET}_18") (pintype "input"))
      (node (ref "IC4") (pin "2") (pinfunction "~{RESET}_2") (pintype "bidirectional"))
    )
    (net (code "55") (name "Net-(IC3A--IN)") (class "Default")
      (node (ref "C26") (pin "1") (pinfunction "1_1") (pintype "passive"))
      (node (ref "IC3") (pin "2") (pinfunction "-IN_2") (pintype "input"))
      (node (ref "R13") (pin "2") (pinfunction "2_2") (pintype "passive"))
      (node (ref "R14") (pin "1") (pinfunction "1_1") (pintype "passive"))
    )
    (net (code "56") (name "Net-(IC3A-OUT)") (class "Default")
      (node (ref "C26") (pin "2") (pinfunction "2_2") (pintype "passive"))
      (node (ref "IC3") (pin "1") (pinfunction "OUT_1") (pintype "output"))
      (node (ref "JP14") (pin "1") (pinfunction "1_1") (pintype "passive"))
      (node (ref "R10") (pin "1") (pinfunction "1_1") (pintype "passive"))
      (node (ref "R14") (pin "2") (pinfunction "2_2") (pintype "passive"))
    )
    (net (code "57") (name "Net-(IC3B--IN)") (class "Default")
      (node (ref "C28") (pin "1") (pinfunction "1_1") (pintype "passive"))
      (node (ref "IC3") (pin "6") (pinfunction "-IN_6") (pintype "input"))
      (node (ref "R15") (pin "1") (pinfunction "1_1") (pintype "passive"))
      (node (ref "R21") (pin "2") (pinfunction "2_2") (pintype "passive"))
    )
    (net (code "58") (name "Net-(IC3B-OUT)") (class "Default")
      (node (ref "C28") (pin "2") (pinfunction "2_2") (pintype "passive"))
      (node (ref "IC3") (pin "7") (pinfunction "OUT_7") (pintype "output"))
      (node (ref "R15") (pin "2") (pinfunction "2_2") (pintype "passive"))
      (node (ref "R22") (pin "1") (pinfunction "1_1") (pintype "passive"))
    )
    (net (code "59") (name "Net-(IC4-~{MR})") (class "Default")
      (node (ref "IC4") (pin "3") (pinfunction "~{MR}_3") (pintype "bidirectional"))
      (node (ref "JP15") (pin "2") (pinfunction "2_2") (pintype "passive"))
      (node (ref "S1") (pin "3") (pinfunction "P_3") (pintype "passive"))
      (node (ref "S1") (pin "4") (pinfunction "P1_4") (pintype "passive"))
    )
    (net (code "60") (name "Net-(IC5A--IN)") (class "Default")
      (node (ref "C57") (pin "1") (pinfunction "1_1") (pintype "passive"))
      (node (ref "IC5") (pin "2") (pinfunction "-IN_2") (pintype "input"))
      (node (ref "R31") (pin "2") (pinfunction "2_2") (pintype "passive"))
      (node (ref "R32") (pin "1") (pinfunction "1_1") (pintype "passive"))
    )
    (net (code "61") (name "Net-(IC5A-OUT)") (class "Default")
      (node (ref "C57") (pin "2") (pinfunction "2_2") (pintype "passive"))
      (node (ref "IC5") (pin "1") (pinfunction "OUT_1") (pintype "output"))
      (node (ref "JP19") (pin "1") (pinfunction "1_1") (pintype "passive"))
      (node (ref "R28") (pin "1") (pinfunction "1_1") (pintype "passive"))
      (node (ref "R32") (pin "2") (pinfunction "2_2") (pintype "passive"))
    )
    (net (code "62") (name "Net-(IC5B--IN)") (class "Default")
      (node (ref "C58") (pin "1") (pinfunction "1_1") (pintype "passive"))
      (node (ref "IC5") (pin "6") (pinfunction "-IN_6") (pintype "input"))
      (node (ref "R33") (pin "1") (pinfunction "1_1") (pintype "passive"))
      (node (ref "R35") (pin "2") (pinfunction "2_2") (pintype "passive"))
    )
    (net (code "63") (name "Net-(IC5B-OUT)") (class "Default")
      (node (ref "C58") (pin "2") (pinfunction "2_2") (pintype "passive"))
      (node (ref "IC5") (pin "7") (pinfunction "OUT_7") (pintype "output"))
      (node (ref "R29") (pin "1") (pinfunction "1_1") (pintype "passive"))
      (node (ref "R33") (pin "2") (pinfunction "2_2") (pintype "passive"))
    )
    (net (code "64") (name "Net-(IC6-FEEDBACK)") (class "Default")
      (node (ref "IC6") (pin "4") (pinfunction "FEEDBACK_4") (pintype "bidirectional"))
      (node (ref "R3") (pin "2") (pinfunction "S_2") (pintype "passive"))
    )
    (net (code "65") (name "Net-(IC6-OUTPUT)") (class "Default")
      (node (ref "D1") (pin "C") (pinfunction "C_C") (pintype "passive"))
      (node (ref "IC6") (pin "2") (pinfunction "OUTPUT_2") (pintype "bidirectional"))
      (node (ref "L1") (pin "1") (pinfunction "1_1") (pintype "passive"))
    )
    (net (code "66") (name "Net-(J1-TIP)") (class "Default")
      (node (ref "C30") (pin "-") (pinfunction "-_-") (pintype "passive"))
      (node (ref "J1") (pin "2") (pinfunction "TIP_2") (pintype "bidirectional"))
      (node (ref "JP13") (pin "3") (pinfunction "3_3") (pintype "passive"))
      (node (ref "R20") (pin "2") (pinfunction "2_2") (pintype "passive"))
    )
    (net (code "67") (name "Net-(J2-TIP)") (class "Default")
      (node (ref "C45") (pin "-") (pinfunction "-_-") (pintype "passive"))
      (node (ref "J2") (pin "2") (pinfunction "TIP_2") (pintype "bidirectional"))
      (node (ref "JP13") (pin "1") (pinfunction "1_1") (pintype "passive"))
      (node (ref "R26") (pin "2") (pinfunction "2_2") (pintype "passive"))
    )
    (net (code "68") (name "Net-(J3-TIP)") (class "Default")
      (node (ref "C59") (pin "-") (pinfunction "-_-") (pintype "passive"))
      (node (ref "J3") (pin "2") (pinfunction "TIP_2") (pintype "bidirectional"))
      (node (ref "JP18") (pin "1") (pinfunction "1_1") (pintype "passive"))
      (node (ref "R34") (pin "2") (pinfunction "2_2") (pintype "passive"))
    )
    (net (code "69") (name "Net-(J4-TIP)") (class "Default")
      (node (ref "C60") (pin "-") (pinfunction "-_-") (pintype "passive"))
      (node (ref "J4") (pin "2") (pinfunction "TIP_2") (pintype "bidirectional"))
      (node (ref "JP18") (pin "3") (pinfunction "3_3") (pintype "passive"))
      (node (ref "R36") (pin "2") (pinfunction "2_2") (pintype "passive"))
    )
    (net (code "70") (name "Net-(JP11-Pad2)") (class "Default")
      (node (ref "JP11") (pin "2") (pinfunction "2_2") (pintype "passive"))
      (node (ref "R19") (pin "2") (pinfunction "2_2") (pintype "passive"))
    )
    (net (code "71") (name "Net-(JP11-Pad4)") (class "Default")
      (node (ref "JP11") (pin "4") (pinfunction "4_4") (pintype "passive"))
      (node (ref "R18") (pin "2") (pinfunction "2_2") (pintype "passive"))
    )
    (net (code "72") (name "Net-(JP11-Pad6)") (class "Default")
      (node (ref "JP11") (pin "6") (pinfunction "6_6") (pintype "passive"))
      (node (ref "R16") (pin "2") (pinfunction "2_2") (pintype "passive"))
    )
    (net (code "73") (name "Net-(JP14-Pad2)") (class "Default")
      (node (ref "JP14") (pin "2") (pinfunction "2_2") (pintype "passive"))
      (node (ref "R21") (pin "1") (pinfunction "1_1") (pintype "passive"))
    )
    (net (code "74") (name "Net-(JP16-Pad1)") (class "Default")
      (node (ref "JP16") (pin "1") (pinfunction "1_1") (pintype "passive"))
      (node (ref "R28") (pin "2") (pinfunction "2_2") (pintype "passive"))
    )
    (net (code "75") (name "Net-(JP17-Pad1)") (class "Default")
      (node (ref "JP17") (pin "1") (pinfunction "1_1") (pintype "passive"))
      (node (ref "R29") (pin "2") (pinfunction "2_2") (pintype "passive"))
    )
    (net (code "76") (name "Net-(JP19-Pad2)") (class "Default")
      (node (ref "JP19") (pin "2") (pinfunction "2_2") (pintype "passive"))
      (node (ref "R35") (pin "1") (pinfunction "1_1") (pintype "passive"))
    )
    (net (code "77") (name "Net-(LED1-PadA)") (class "Default")
      (node (ref "LED1") (pin "A") (pinfunction "A_A") (pintype "passive"))
      (node (ref "R2") (pin "2") (pinfunction "2_2") (pintype "passive"))
    )
    (net (code "78") (name "Net-(LED3-PadA)") (class "Default")
      (node (ref "LED3") (pin "A") (pinfunction "A_A") (pintype "passive"))
      (node (ref "R4") (pin "2") (pinfunction "2_2") (pintype "passive"))
    )
    (net (code "79") (name "Net-(LED4-PadA)") (class "Default")
      (node (ref "LED4") (pin "A") (pinfunction "A_A") (pintype "passive"))
      (node (ref "R5") (pin "2") (pinfunction "2_2") (pintype "passive"))
    )
    (net (code "80") (name "Net-(LED5-PadA)") (class "Default")
      (node (ref "LED5") (pin "A") (pinfunction "A_A") (pintype "passive"))
      (node (ref "R6") (pin "2") (pinfunction "2_2") (pintype "passive"))
    )
    (net (code "81") (name "Net-(R3-A)") (class "Default")
      (node (ref "C3") (pin "+") (pinfunction "+_+") (pintype "passive"))
      (node (ref "JP1") (pin "2") (pinfunction "2_2") (pintype "passive"))
      (node (ref "JP2") (pin "2") (pinfunction "2_2") (pintype "passive"))
      (node (ref "JP3") (pin "2") (pinfunction "2_2") (pintype "passive"))
      (node (ref "L1") (pin "2") (pinfunction "2_2") (pintype "passive"))
      (node (ref "R3") (pin "1") (pinfunction "A_1") (pintype "passive"))
    )
    (net (code "82") (name "PVDD") (class "Default")
      (node (ref "C15") (pin "+") (pinfunction "+_+") (pintype "passive"))
      (node (ref "C16") (pin "1") (pinfunction "1_1") (pintype "passive"))
      (node (ref "C17") (pin "1") (pinfunction "1_1") (pintype "passive"))
      (node (ref "C54") (pin "1") (pinfunction "1_1") (pintype "passive"))
      (node (ref "C55") (pin "1") (pinfunction "1_1") (pintype "passive"))
      (node (ref "C56") (pin "+") (pinfunction "+_+") (pintype "passive"))
      (node (ref "C61") (pin "1") (pinfunction "1_1") (pintype "passive"))
      (node (ref "C62") (pin "1") (pinfunction "1_1") (pintype "passive"))
      (node (ref "C63") (pin "1") (pinfunction "1_1") (pintype "passive"))
      (node (ref "C64") (pin "1") (pinfunction "1_1") (pintype "passive"))
      (node (ref "IC2") (pin "29") (pinfunction "PVDD_CD_1_29") (pintype "power_in"))
      (node (ref "IC2") (pin "30") (pinfunction "PVDD_CD_2_30") (pintype "power_in"))
      (node (ref "IC2") (pin "31") (pinfunction "PVDD_CD_3_31") (pintype "power_in"))
      (node (ref "IC2") (pin "36") (pinfunction "PVDD_AB_1_36") (pintype "power_in"))
      (node (ref "IC2") (pin "37") (pinfunction "PVDD_AB_2_37") (pintype "power_in"))
      (node (ref "IC2") (pin "38") (pinfunction "PVDD_AB_3_38") (pintype "power_in"))
      (node (ref "JP5") (pin "2") (pinfunction "2_2") (pintype "passive"))
      (node (ref "JP6") (pin "2") (pinfunction "2_2") (pintype "passive"))
      (node (ref "JP7") (pin "2") (pinfunction "2_2") (pintype "passive"))
      (node (ref "JP8") (pin "2") (pinfunction "2_2") (pintype "passive"))
    )
    (net (code "83") (name "SUPPLY2_GND") (class "Default")
      (node (ref "C1") (pin "-") (pinfunction "-_-") (pintype "passive"))
      (node (ref "C10") (pin "1") (pinfunction "1_1") (pintype "passive"))
      (node (ref "C11") (pin "1") (pinfunction "1_1") (pintype "passive"))
      (node (ref "C12") (pin "1") (pinfunction "1_1") (pintype "passive"))
      (node (ref "C13") (pin "1") (pinfunction "1_1") (pintype "passive"))
      (node (ref "C14") (pin "1") (pinfunction "1_1") (pintype "passive"))
      (node (ref "C15") (pin "-") (pinfunction "-_-") (pintype "passive"))
      (node (ref "C16") (pin "2") (pinfunction "2_2") (pintype "passive"))
      (node (ref "C17") (pin "2") (pinfunction "2_2") (pintype "passive"))
      (node (ref "C18") (pin "1") (pinfunction "1_1") (pintype "passive"))
      (node (ref "C19") (pin "2") (pinfunction "2_2") (pintype "passive"))
      (node (ref "C2") (pin "2") (pinfunction "2_2") (pintype "passive"))
      (node (ref "C23") (pin "2") (pinfunction "2_2") (pintype "passive"))
      (node (ref "C24") (pin "2") (pinfunction "2_2") (pintype "passive"))
      (node (ref "C29") (pin "2") (pinfunction "2_2") (pintype "passive"))
      (node (ref "C3") (pin "-") (pinfunction "-_-") (pintype "passive"))
      (node (ref "C31") (pin "1") (pinfunction "1_1") (pintype "passive"))
      (node (ref "C33") (pin "2") (pinfunction "2_2") (pintype "passive"))
      (node (ref "C34") (pin "2") (pinfunction "2_2") (pintype "passive"))
      (node (ref "C35") (pin "2") (pinfunction "2_2") (pintype "passive"))
      (node (ref "C36") (pin "1") (pinfunction "1_1") (pintype "passive"))
      (node (ref "C38") (pin "2") (pinfunction "2_2") (pintype "passive"))
      (node (ref "C39") (pin "2") (pinfunction "2_2") (pintype "passive"))
      (node (ref "C4") (pin "-") (pinfunction "-_-") (pintype "passive"))
      (node (ref "C42") (pin "1") (pinfunction "1_1") (pintype "passive"))
      (node (ref "C43") (pin "2") (pinfunction "2_2") (pintype "passive"))
      (node (ref "C47") (pin "2") (pinfunction "2_2") (pintype "passive"))
      (node (ref "C49") (pin "2") (pinfunction "2_2") (pintype "passive"))
      (node (ref "C51") (pin "2") (pinfunction "2_2") (pintype "passive"))
      (node (ref "C52") (pin "2") (pinfunction "2_2") (pintype "passive"))
      (node (ref "C54") (pin "2") (pinfunction "2_2") (pintype "passive"))
      (node (ref "C55") (pin "2") (pinfunction "2_2") (pintype "passive"))
      (node (ref "C56") (pin "-") (pinfunction "-_-") (pintype "passive"))
      (node (ref "C6") (pin "2") (pinfunction "2_2") (pintype "passive"))
      (node (ref "C61") (pin "2") (pinfunction "2_2") (pintype "passive"))
      (node (ref "C62") (pin "2") (pinfunction "2_2") (pintype "passive"))
      (node (ref "C63") (pin "2") (pinfunction "2_2") (pintype "passive"))
      (node (ref "C64") (pin "2") (pinfunction "2_2") (pintype "passive"))
      (node (ref "C65") (pin "2") (pinfunction "2_2") (pintype "passive"))
      (node (ref "C66") (pin "2") (pinfunction "2_2") (pintype "passive"))
      (node (ref "C67") (pin "2") (pinfunction "2_2") (pintype "passive"))
      (node (ref "C68") (pin "2") (pinfunction "2_2") (pintype "passive"))
      (node (ref "C7") (pin "2") (pinfunction "2_2") (pintype "passive"))
      (node (ref "C9") (pin "1") (pinfunction "1_1") (pintype "passive"))
      (node (ref "D1") (pin "A") (pinfunction "A_A") (pintype "passive"))
      (node (ref "IC1") (pin "1") (pinfunction "GROUND/ADJUST_1") (pintype "bidirectional"))
      (node (ref "IC2") (pin "12") (pinfunction "GND_1_12") (pintype "power_in"))
      (node (ref "IC2") (pin "13") (pinfunction "GND_2_13") (pintype "power_in"))
      (node (ref "IC2") (pin "25") (pinfunction "GND_3_25") (pintype "power_in"))
      (node (ref "IC2") (pin "26") (pinfunction "GND_4_26") (pintype "power_in"))
      (node (ref "IC2") (pin "33") (pinfunction "GND_5_33") (pintype "power_in"))
      (node (ref "IC2") (pin "34") (pinfunction "GND_6_34") (pintype "power_in"))
      (node (ref "IC2") (pin "41") (pinfunction "GND_7_41") (pintype "power_in"))
      (node (ref "IC2") (pin "42") (pinfunction "GND_8_42") (pintype "power_in"))
      (node (ref "IC3") (pin "4") (pinfunction "V-_4") (pintype "power_in"))
      (node (ref "IC4") (pin "1") (pinfunction "GND_1") (pintype "power_in"))
      (node (ref "IC5") (pin "4") (pinfunction "V-_4") (pintype "power_in"))
      (node (ref "IC6") (pin "3") (pinfunction "GND_3") (pintype "bidirectional"))
      (node (ref "IC6") (pin "5") (pinfunction "~{ON}/OFF_5") (pintype "bidirectional"))
      (node (ref "J1") (pin "1") (pinfunction "SLEEVE_1") (pintype "bidirectional"))
      (node (ref "J1") (pin "3") (pinfunction "SHUNT_3") (pintype "bidirectional"))
      (node (ref "J2") (pin "1") (pinfunction "SLEEVE_1") (pintype "bidirectional"))
      (node (ref "J2") (pin "3") (pinfunction "SHUNT_3") (pintype "bidirectional"))
      (node (ref "J3") (pin "1") (pinfunction "SLEEVE_1") (pintype "bidirectional"))
      (node (ref "J3") (pin "3") (pinfunction "SHUNT_3") (pintype "bidirectional"))
      (node (ref "J4") (pin "1") (pinfunction "SLEEVE_1") (pintype "bidirectional"))
      (node (ref "J4") (pin "3") (pinfunction "SHUNT_3") (pintype "bidirectional"))
      (node (ref "JP10") (pin "1") (pinfunction "1_1") (pintype "passive"))
      (node (ref "JP13") (pin "2") (pinfunction "2_2") (pintype "passive"))
      (node (ref "JP15") (pin "1") (pinfunction "1_1") (pintype "passive"))
      (node (ref "JP18") (pin "2") (pinfunction "2_2") (pintype "passive"))
      (node (ref "JP9") (pin "1") (pinfunction "1_1") (pintype "passive"))
      (node (ref "LED1") (pin "C") (pinfunction "C_C") (pintype "passive"))
      (node (ref "LED3") (pin "C") (pinfunction "C_C") (pintype "passive"))
      (node (ref "R12") (pin "2") (pinfunction "2_2") (pintype "passive"))
      (node (ref "R16") (pin "1") (pinfunction "1_1") (pintype "passive"))
      (node (ref "R17") (pin "1") (pinfunction "1_1") (pintype "passive"))
      (node (ref "R18") (pin "1") (pinfunction "1_1") (pintype "passive"))
      (node (ref "R19") (pin "1") (pinfunction "1_1") (pintype "passive"))
      (node (ref "R20") (pin "1") (pinfunction "1_1") (pintype "passive"))
      (node (ref "R25") (pin "1") (pinfunction "1_1") (pintype "passive"))
      (node (ref "R26") (pin "1") (pinfunction "1_1") (pintype "passive"))
      (node (ref "R3") (pin "3") (pinfunction "E_3") (pintype "passive"))
      (node (ref "R30") (pin "1") (pinfunction "1_1") (pintype "passive"))
      (node (ref "R34") (pin "1") (pinfunction "1_1") (pintype "passive"))
      (node (ref "R36") (pin "1") (pinfunction "1_1") (pintype "passive"))
      (node (ref "R8") (pin "1") (pinfunction "1_1") (pintype "passive"))
      (node (ref "R9") (pin "1") (pinfunction "1_1") (pintype "passive"))
      (node (ref "S1") (pin "1") (pinfunction "S_1") (pintype "passive"))
      (node (ref "S1") (pin "2") (pinfunction "S1_2") (pintype "passive"))
      (node (ref "T1") (pin "P$1") (pinfunction "P$1_P$1") (pintype "bidirectional"))
      (node (ref "U$1") (pin "P$1") (pinfunction "P$1_P$1") (pintype "bidirectional"))
      (node (ref "U$2") (pin "P$1") (pinfunction "P$1_P$1") (pintype "bidirectional"))
    )
    (net (code "84") (name "VMID") (class "Default")
      (node (ref "C10") (pin "2") (pinfunction "2_2") (pintype "passive"))
      (node (ref "C9") (pin "2") (pinfunction "2_2") (pintype "passive"))
      (node (ref "IC3") (pin "3") (pinfunction "+IN_3") (pintype "input"))
      (node (ref "IC3") (pin "5") (pinfunction "+IN_5") (pintype "input"))
      (node (ref "IC5") (pin "3") (pinfunction "+IN_3") (pintype "input"))
      (node (ref "IC5") (pin "5") (pinfunction "+IN_5") (pintype "input"))
      (node (ref "R7") (pin "2") (pinfunction "2_2") (pintype "passive"))
      (node (ref "R8") (pin "2") (pinfunction "2_2") (pintype "passive"))
    )
    (net (code "85") (name "unconnected-(IC2-EP-Pad45)") (class "Default")
      (node (ref "IC2") (pin "45") (pinfunction "EP_45") (pintype "bidirectional"))
    )
    (net (code "86") (name "unconnected-(IC2-OCS_IOP-Pad10)") (class "Default")
      (node (ref "IC2") (pin "10") (pinfunction "OCS_IOP_10") (pintype "output"))
    )
    (net (code "87") (name "unconnected-(IC2-OSC_IOM-Pad9)") (class "Default")
      (node (ref "IC2") (pin "9") (pinfunction "OSC_IOM_9") (pintype "bidirectional"))
    )
  )
)
